# LTC4156Shield.net
KiCad netlist of a schematic drawn in EAGLE
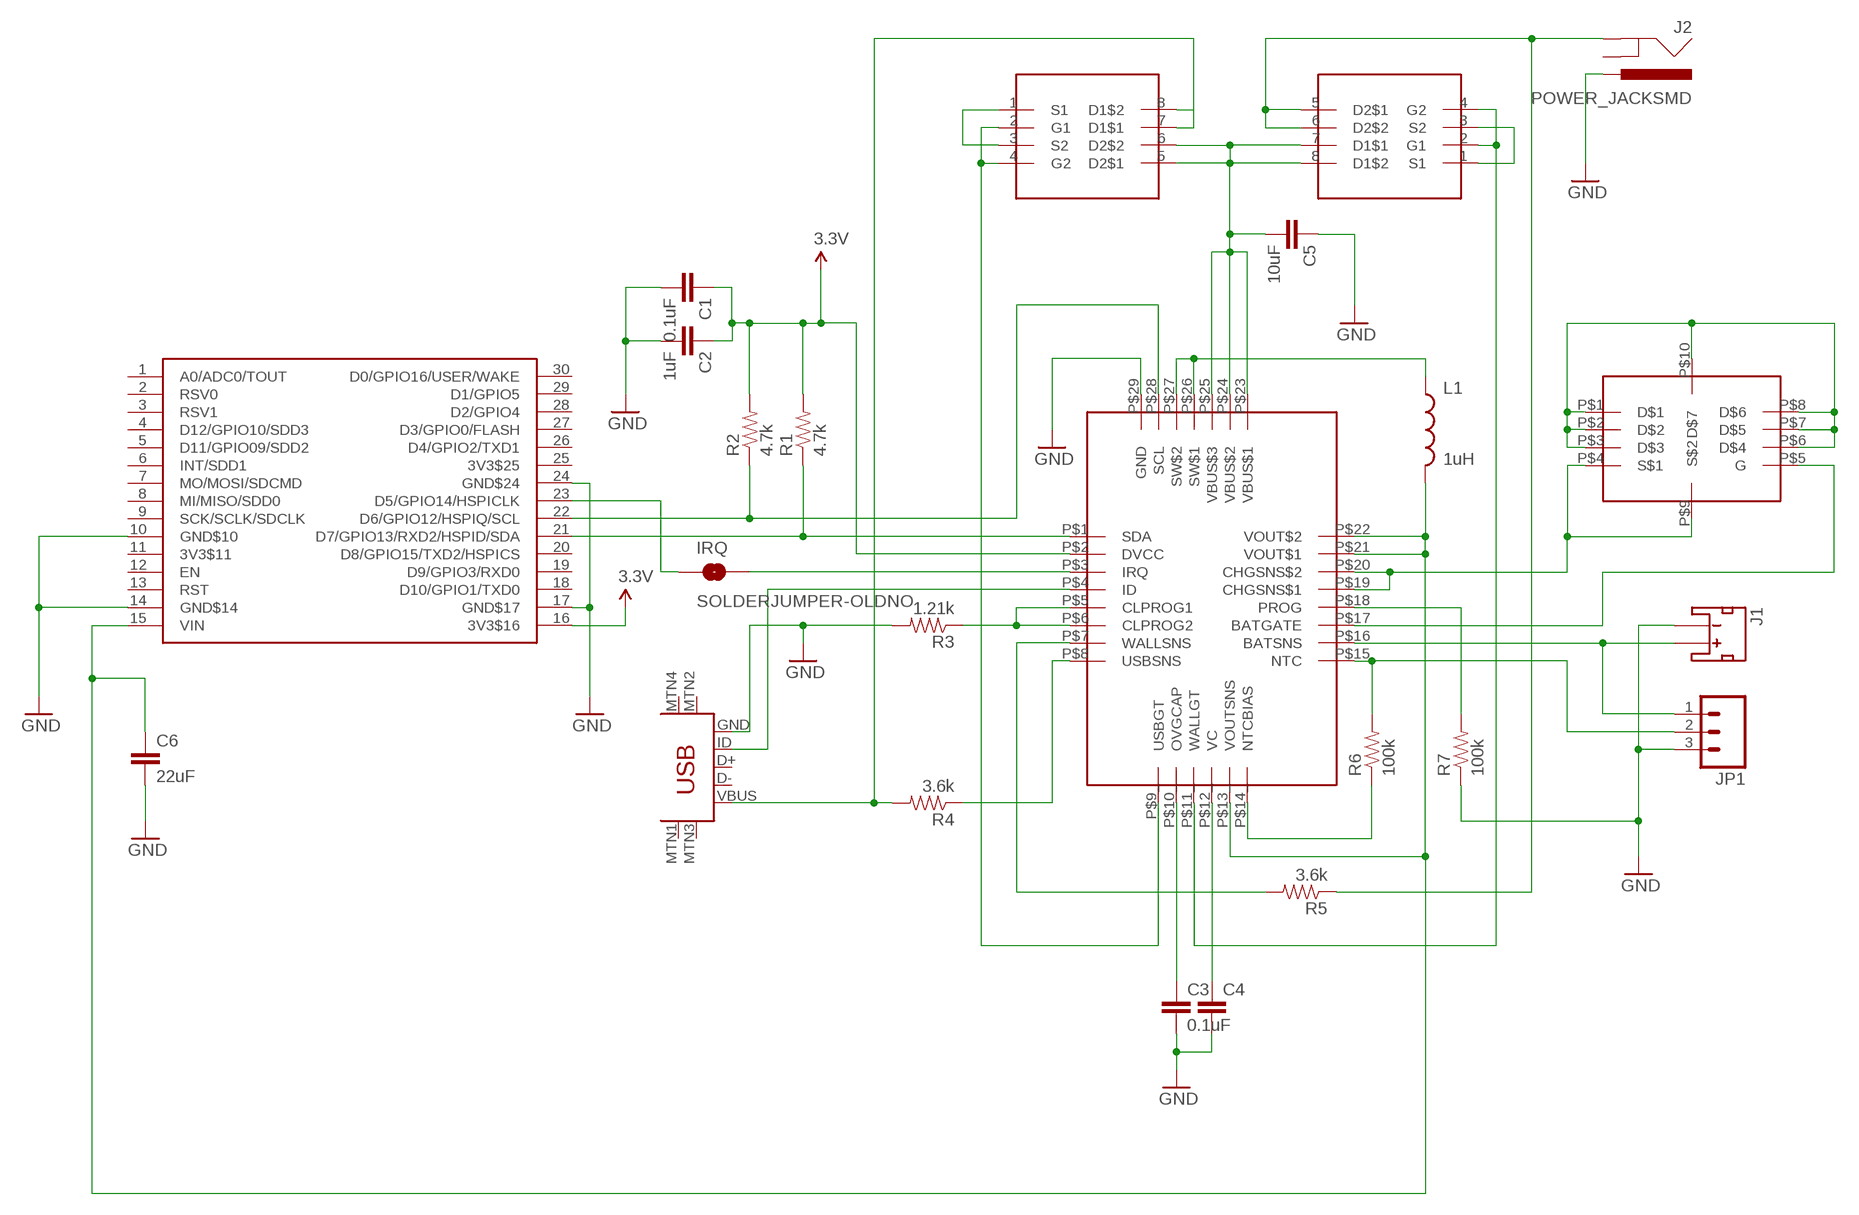
[diagram p0: schematic, sheet 1]

(export (version "E")
  (design (tool "Eeschema 10.0.6"))
  (components
    (comp (ref "C1")
      (value "0.1uF")
      (footprint "eagle-import:0402-CAP")
      (libsource (lib "eagle-import") (part "CAP0402-CAP"))
    )
    (comp (ref "C2")
      (value "1uF")
      (footprint "eagle-import:0402-CAP")
      (libsource (lib "eagle-import") (part "CAP0402-CAP"))
    )
    (comp (ref "C3")
      (value "0.1uF")
      (footprint "eagle-import:0402-CAP")
      (libsource (lib "eagle-import") (part "CAP0402-CAP"))
    )
    (comp (ref "C4")
      (value "CAP0805")
      (footprint "eagle-import:0805")
      (libsource (lib "eagle-import") (part "SparkFun-Capacitors_CAP0805"))
    )
    (comp (ref "C5")
      (value "10uF")
      (footprint "eagle-import:0402-CAP")
      (libsource (lib "eagle-import") (part "CAP0402-CAP"))
    )
    (comp (ref "C6")
      (value "22uF")
      (footprint "eagle-import:0402-CAP")
      (libsource (lib "eagle-import") (part "CAP0402-CAP"))
    )
    (comp (ref "IRQ")
      (value "SOLDERJUMPER-OLDNO")
      (footprint "eagle-import:SJ_2S-NO")
      (libsource (lib "eagle-import") (part "SOLDERJUMPER-OLDNO"))
    )
    (comp (ref "J1")
      (value "JST_2MM_MALE")
      (footprint "eagle-import:JST-2-SMD")
      (libsource (lib "eagle-import") (part "JST_2MM_MALE"))
    )
    (comp (ref "J2")
      (value "POWER_JACKSMD")
      (footprint "eagle-import:POWER_JACK_SMD")
      (libsource (lib "eagle-import") (part "POWER_JACKSMD"))
    )
    (comp (ref "JP1")
      (value "M03")
      (footprint "eagle-import:JST-3-SMD")
      (libsource (lib "eagle-import") (part "M03"))
    )
    (comp (ref "L1")
      (value "1uH")
      (footprint "eagle-import:0805")
      (libsource (lib "eagle-import") (part "INDUCTOR0805"))
    )
    (comp (ref "R1")
      (value "4.7k")
      (footprint "eagle-import:0402-RES")
      (libsource (lib "eagle-import") (part "RESISTOR0402-RES"))
    )
    (comp (ref "R2")
      (value "4.7k")
      (footprint "eagle-import:0402-RES")
      (libsource (lib "eagle-import") (part "RESISTOR0402-RES"))
    )
    (comp (ref "R3")
      (value "1.21k")
      (footprint "eagle-import:0402-RES")
      (libsource (lib "eagle-import") (part "RESISTOR0402-RES"))
    )
    (comp (ref "R4")
      (value "3.6k")
      (footprint "eagle-import:0402-RES")
      (libsource (lib "eagle-import") (part "RESISTOR0402-RES"))
    )
    (comp (ref "R5")
      (value "3.6k")
      (footprint "eagle-import:0402-RES")
      (libsource (lib "eagle-import") (part "RESISTOR0402-RES"))
    )
    (comp (ref "R6")
      (value "100k")
      (footprint "eagle-import:0402-RES")
      (libsource (lib "eagle-import") (part "RESISTOR0402-RES"))
    )
    (comp (ref "R7")
      (value "100k")
      (footprint "eagle-import:0402-RES")
      (libsource (lib "eagle-import") (part "RESISTOR0402-RES"))
    )
    (comp (ref "U$1")
      (value "NERDSHIELD")
      (footprint "eagle-import:NERDUINO_STACK")
      (libsource (lib "eagle-import") (part "NERDSHIELD"))
    )
    (comp (ref "U$2")
      (value "LTC4156")
      (footprint "eagle-import:QFN28")
      (libsource (lib "eagle-import") (part "LTC4156"))
    )
    (comp (ref "U$3")
      (value "SI7938DP")
      (footprint "eagle-import:SO08")
      (libsource (lib "eagle-import") (part "SI7938DP"))
    )
    (comp (ref "U$4")
      (value "USB-MINIB-5PIN")
      (footprint "eagle-import:USB-MINIB")
      (libsource (lib "eagle-import") (part "USB-MINIB-5PIN"))
    )
    (comp (ref "U$5")
      (value "SI7938DP")
      (footprint "eagle-import:SO08")
      (libsource (lib "eagle-import") (part "SI7938DP"))
    )
    (comp (ref "U$6")
      (value "SI5481")
      (footprint "eagle-import:SI5481")
      (libsource (lib "eagle-import") (part "SI5481"))
    )
  )
  (nets
    (net (code "1") (name "3.3V") (class "Default")
      (node (ref "C1") (pin "1") (pinfunction "1_1") (pintype "passive"))
      (node (ref "C2") (pin "1") (pinfunction "1_1") (pintype "passive"))
      (node (ref "R1") (pin "2") (pinfunction "2_2") (pintype "passive"))
      (node (ref "R2") (pin "2") (pinfunction "2_2") (pintype "passive"))
      (node (ref "U$1") (pin "16") (pinfunction "3V3$16_16") (pintype "bidirectional"))
      (node (ref "U$2") (pin "P$2") (pinfunction "DVCC_P$2") (pintype "bidirectional"))
    )
    (net (code "2") (name "GND") (class "Default")
      (node (ref "C1") (pin "2") (pinfunction "2_2") (pintype "passive"))
      (node (ref "C2") (pin "2") (pinfunction "2_2") (pintype "passive"))
      (node (ref "C3") (pin "2") (pinfunction "2_2") (pintype "passive"))
      (node (ref "C4") (pin "2") (pinfunction "2_2") (pintype "passive"))
      (node (ref "C5") (pin "1") (pinfunction "1_1") (pintype "passive"))
      (node (ref "C6") (pin "2") (pinfunction "2_2") (pintype "passive"))
      (node (ref "J1") (pin "1") (pinfunction "-_1") (pintype "bidirectional"))
      (node (ref "J2") (pin "VIN0") (pinfunction "PWR_VIN0") (pintype "bidirectional"))
      (node (ref "JP1") (pin "3") (pinfunction "3_3") (pintype "passive"))
      (node (ref "R3") (pin "2") (pinfunction "2_2") (pintype "passive"))
      (node (ref "R7") (pin "1") (pinfunction "1_1") (pintype "passive"))
      (node (ref "U$1") (pin "10") (pinfunction "GND$10_10") (pintype "bidirectional"))
      (node (ref "U$1") (pin "14") (pinfunction "GND$14_14") (pintype "bidirectional"))
      (node (ref "U$1") (pin "17") (pinfunction "GND$17_17") (pintype "bidirectional"))
      (node (ref "U$1") (pin "24") (pinfunction "GND$24_24") (pintype "bidirectional"))
      (node (ref "U$2") (pin "P$29") (pinfunction "GND_P$29") (pintype "bidirectional"))
      (node (ref "U$4") (pin "GND") (pinfunction "GND_GND") (pintype "bidirectional"))
    )
    (net (code "3") (name "Net-(J1-+)") (class "Default")
      (node (ref "J1") (pin "2") (pinfunction "+_2") (pintype "bidirectional"))
      (node (ref "JP1") (pin "1") (pinfunction "1_1") (pintype "passive"))
      (node (ref "U$2") (pin "P$16") (pinfunction "BATSNS_P$16") (pintype "bidirectional"))
    )
    (net (code "4") (name "Net-(J2-GND)") (class "Default")
      (node (ref "J2") (pin "P$4") (pinfunction "GND_P$4") (pintype "bidirectional"))
      (node (ref "R5") (pin "1") (pinfunction "1_1") (pintype "passive"))
      (node (ref "U$5") (pin "5") (pinfunction "D2$1_5") (pintype "bidirectional"))
      (node (ref "U$5") (pin "6") (pinfunction "D2$2_6") (pintype "bidirectional"))
    )
    (net (code "5") (name "Net-(U$1-D5{slash}GPIO14{slash}HSPICLK)") (class "Default")
      (node (ref "IRQ") (pin "1") (pinfunction "1_1") (pintype "passive"))
      (node (ref "U$1") (pin "23") (pinfunction "D5/GPIO14/HSPICLK_23") (pintype "bidirectional"))
    )
    (net (code "6") (name "Net-(U$1-D6{slash}GPIO12{slash}HSPIQ{slash}SCL)") (class "Default")
      (node (ref "R2") (pin "1") (pinfunction "1_1") (pintype "passive"))
      (node (ref "U$1") (pin "22") (pinfunction "D6/GPIO12/HSPIQ/SCL_22") (pintype "bidirectional"))
      (node (ref "U$2") (pin "P$28") (pinfunction "SCL_P$28") (pintype "bidirectional"))
    )
    (net (code "7") (name "Net-(U$1-D7{slash}GPIO13{slash}RXD2{slash}HSPID{slash}SDA)") (class "Default")
      (node (ref "R1") (pin "1") (pinfunction "1_1") (pintype "passive"))
      (node (ref "U$1") (pin "21") (pinfunction "D7/GPIO13/RXD2/HSPID/SDA_21") (pintype "bidirectional"))
      (node (ref "U$2") (pin "P$1") (pinfunction "SDA_P$1") (pintype "bidirectional"))
    )
    (net (code "8") (name "Net-(U$1-VIN)") (class "Default")
      (node (ref "C6") (pin "1") (pinfunction "1_1") (pintype "passive"))
      (node (ref "L1") (pin "2") (pinfunction "2_2") (pintype "passive"))
      (node (ref "U$1") (pin "15") (pinfunction "VIN_15") (pintype "bidirectional"))
      (node (ref "U$2") (pin "P$13_") (pinfunction "VOUTSNS_P$13_") (pintype "bidirectional"))
      (node (ref "U$2") (pin "P$21") (pinfunction "VOUT$1_P$21") (pintype "bidirectional"))
      (node (ref "U$2") (pin "P$22") (pinfunction "VOUT$2_P$22") (pintype "bidirectional"))
    )
    (net (code "9") (name "Net-(U$2-BATGATE)") (class "Default")
      (node (ref "U$2") (pin "P$17") (pinfunction "BATGATE_P$17") (pintype "bidirectional"))
      (node (ref "U$6") (pin "P$5") (pinfunction "G_P$5") (pintype "bidirectional"))
    )
    (net (code "10") (name "Net-(U$2-CHGSNS$1)") (class "Default")
      (node (ref "U$2") (pin "P$19") (pinfunction "CHGSNS$1_P$19") (pintype "bidirectional"))
      (node (ref "U$2") (pin "P$20") (pinfunction "CHGSNS$2_P$20") (pintype "bidirectional"))
      (node (ref "U$6") (pin "P$4") (pinfunction "S$1_P$4") (pintype "bidirectional"))
      (node (ref "U$6") (pin "P$9") (pinfunction "S$2_P$9") (pintype "bidirectional"))
    )
    (net (code "11") (name "Net-(U$2-CLPROG1)") (class "Default")
      (node (ref "R3") (pin "1") (pinfunction "1_1") (pintype "passive"))
      (node (ref "U$2") (pin "P$5") (pinfunction "CLPROG1_P$5") (pintype "bidirectional"))
      (node (ref "U$2") (pin "P$6") (pinfunction "CLPROG2_P$6") (pintype "bidirectional"))
    )
    (net (code "12") (name "Net-(U$2-ID)") (class "Default")
      (node (ref "U$2") (pin "P$4") (pinfunction "ID_P$4") (pintype "bidirectional"))
      (node (ref "U$4") (pin "ID") (pinfunction "ID_ID") (pintype "bidirectional"))
    )
    (net (code "13") (name "Net-(U$2-IRQ)") (class "Default")
      (node (ref "IRQ") (pin "2") (pinfunction "2_2") (pintype "passive"))
      (node (ref "U$2") (pin "P$3") (pinfunction "IRQ_P$3") (pintype "bidirectional"))
    )
    (net (code "14") (name "Net-(U$2-NTC)") (class "Default")
      (node (ref "JP1") (pin "2") (pinfunction "2_2") (pintype "passive"))
      (node (ref "R6") (pin "2") (pinfunction "2_2") (pintype "passive"))
      (node (ref "U$2") (pin "P$15") (pinfunction "NTC_P$15") (pintype "bidirectional"))
    )
    (net (code "15") (name "Net-(U$2-NTCBIAS)") (class "Default")
      (node (ref "R6") (pin "1") (pinfunction "1_1") (pintype "passive"))
      (node (ref "U$2") (pin "P$14_") (pinfunction "NTCBIAS_P$14_") (pintype "bidirectional"))
    )
    (net (code "16") (name "Net-(U$2-OVGCAP)") (class "Default")
      (node (ref "C3") (pin "1") (pinfunction "1_1") (pintype "passive"))
      (node (ref "U$2") (pin "P$10_") (pinfunction "OVGCAP_P$10_") (pintype "bidirectional"))
    )
    (net (code "17") (name "Net-(U$2-PROG)") (class "Default")
      (node (ref "R7") (pin "2") (pinfunction "2_2") (pintype "passive"))
      (node (ref "U$2") (pin "P$18") (pinfunction "PROG_P$18") (pintype "bidirectional"))
    )
    (net (code "18") (name "Net-(U$2-SW$1)") (class "Default")
      (node (ref "L1") (pin "1") (pinfunction "1_1") (pintype "passive"))
      (node (ref "U$2") (pin "P$26") (pinfunction "SW$1_P$26") (pintype "bidirectional"))
      (node (ref "U$2") (pin "P$27") (pinfunction "SW$2_P$27") (pintype "bidirectional"))
    )
    (net (code "19") (name "Net-(U$2-USBGT)") (class "Default")
      (node (ref "U$2") (pin "P$9_") (pinfunction "USBGT_P$9_") (pintype "bidirectional"))
      (node (ref "U$3") (pin "2") (pinfunction "G1_2") (pintype "bidirectional"))
      (node (ref "U$3") (pin "4") (pinfunction "G2_4") (pintype "bidirectional"))
    )
    (net (code "20") (name "Net-(U$2-USBSNS)") (class "Default")
      (node (ref "R4") (pin "1") (pinfunction "1_1") (pintype "passive"))
      (node (ref "U$2") (pin "P$8") (pinfunction "USBSNS_P$8") (pintype "bidirectional"))
    )
    (net (code "21") (name "Net-(U$2-VBUS$1)") (class "Default")
      (node (ref "C5") (pin "2") (pinfunction "2_2") (pintype "passive"))
      (node (ref "U$2") (pin "P$23") (pinfunction "VBUS$1_P$23") (pintype "bidirectional"))
      (node (ref "U$2") (pin "P$24") (pinfunction "VBUS$2_P$24") (pintype "bidirectional"))
      (node (ref "U$2") (pin "P$25") (pinfunction "VBUS$3_P$25") (pintype "bidirectional"))
      (node (ref "U$3") (pin "5") (pinfunction "D2$1_5") (pintype "bidirectional"))
      (node (ref "U$3") (pin "6") (pinfunction "D2$2_6") (pintype "bidirectional"))
      (node (ref "U$5") (pin "7") (pinfunction "D1$1_7") (pintype "bidirectional"))
      (node (ref "U$5") (pin "8") (pinfunction "D1$2_8") (pintype "bidirectional"))
    )
    (net (code "22") (name "Net-(U$2-VC)") (class "Default")
      (node (ref "C4") (pin "1") (pinfunction "1_1") (pintype "passive"))
      (node (ref "U$2") (pin "P$12_") (pinfunction "VC_P$12_") (pintype "bidirectional"))
    )
    (net (code "23") (name "Net-(U$2-WALLGT)") (class "Default")
      (node (ref "U$2") (pin "P$11_") (pinfunction "WALLGT_P$11_") (pintype "bidirectional"))
      (node (ref "U$5") (pin "2") (pinfunction "G1_2") (pintype "bidirectional"))
      (node (ref "U$5") (pin "4") (pinfunction "G2_4") (pintype "bidirectional"))
    )
    (net (code "24") (name "Net-(U$2-WALLSNS)") (class "Default")
      (node (ref "R5") (pin "2") (pinfunction "2_2") (pintype "passive"))
      (node (ref "U$2") (pin "P$7") (pinfunction "WALLSNS_P$7") (pintype "bidirectional"))
    )
    (net (code "25") (name "Net-(U$3-D1$1)") (class "Default")
      (node (ref "R4") (pin "2") (pinfunction "2_2") (pintype "passive"))
      (node (ref "U$3") (pin "7") (pinfunction "D1$1_7") (pintype "bidirectional"))
      (node (ref "U$3") (pin "8") (pinfunction "D1$2_8") (pintype "bidirectional"))
      (node (ref "U$4") (pin "VBUS") (pinfunction "VBUS_VBUS") (pintype "bidirectional"))
    )
    (net (code "26") (name "Net-(U$3-S1)") (class "Default")
      (node (ref "U$3") (pin "1") (pinfunction "S1_1") (pintype "bidirectional"))
      (node (ref "U$3") (pin "3") (pinfunction "S2_3") (pintype "bidirectional"))
    )
    (net (code "27") (name "Net-(U$5-S1)") (class "Default")
      (node (ref "U$5") (pin "1") (pinfunction "S1_1") (pintype "bidirectional"))
      (node (ref "U$5") (pin "3") (pinfunction "S2_3") (pintype "bidirectional"))
    )
    (net (code "28") (name "Net-(U$6-D$1)") (class "Default")
      (node (ref "U$6") (pin "P$1") (pinfunction "D$1_P$1") (pintype "bidirectional"))
      (node (ref "U$6") (pin "P$10") (pinfunction "D$7_P$10") (pintype "bidirectional"))
      (node (ref "U$6") (pin "P$2") (pinfunction "D$2_P$2") (pintype "bidirectional"))
      (node (ref "U$6") (pin "P$3") (pinfunction "D$3_P$3") (pintype "bidirectional"))
      (node (ref "U$6") (pin "P$6") (pinfunction "D$4_P$6") (pintype "bidirectional"))
      (node (ref "U$6") (pin "P$7") (pinfunction "D$5_P$7") (pintype "bidirectional"))
      (node (ref "U$6") (pin "P$8") (pinfunction "D$6_P$8") (pintype "bidirectional"))
    )
    (net (code "29") (name "unconnected-(J1-PAD1-PadNC1)") (class "Default")
      (node (ref "J1") (pin "NC1") (pinfunction "PAD1_NC1") (pintype "bidirectional"))
    )
    (net (code "30") (name "unconnected-(J1-PAD2-PadNC2)") (class "Default")
      (node (ref "J1") (pin "NC2") (pinfunction "PAD2_NC2") (pintype "bidirectional"))
    )
    (net (code "31") (name "unconnected-(J2-GNDBREAK-PadGND)") (class "Default")
      (node (ref "J2") (pin "GND") (pinfunction "GNDBREAK_GND") (pintype "bidirectional"))
    )
    (net (code "32") (name "unconnected-(U$1-3V3$11-Pad11)") (class "Default")
      (node (ref "U$1") (pin "11") (pinfunction "3V3$11_11") (pintype "bidirectional"))
    )
    (net (code "33") (name "unconnected-(U$1-3V3$25-Pad25)") (class "Default")
      (node (ref "U$1") (pin "25") (pinfunction "3V3$25_25") (pintype "bidirectional"))
    )
    (net (code "34") (name "unconnected-(U$1-A0{slash}ADC0{slash}TOUT-Pad1)") (class "Default")
      (node (ref "U$1") (pin "1") (pinfunction "A0/ADC0/TOUT_1") (pintype "bidirectional"))
    )
    (net (code "35") (name "unconnected-(U$1-D0{slash}GPIO16{slash}USER{slash}WAKE-Pad30)") (class "Default")
      (node (ref "U$1") (pin "30") (pinfunction "D0/GPIO16/USER/WAKE_30") (pintype "bidirectional"))
    )
    (net (code "36") (name "unconnected-(U$1-D1{slash}GPIO5-Pad29)") (class "Default")
      (node (ref "U$1") (pin "29") (pinfunction "D1/GPIO5_29") (pintype "bidirectional"))
    )
    (net (code "37") (name "unconnected-(U$1-D2{slash}GPIO4-Pad28)") (class "Default")
      (node (ref "U$1") (pin "28") (pinfunction "D2/GPIO4_28") (pintype "bidirectional"))
    )
    (net (code "38") (name "unconnected-(U$1-D3{slash}GPIO0{slash}FLASH-Pad27)") (class "Default")
      (node (ref "U$1") (pin "27") (pinfunction "D3/GPIO0/FLASH_27") (pintype "bidirectional"))
    )
    (net (code "39") (name "unconnected-(U$1-D4{slash}GPIO2{slash}TXD1-Pad26)") (class "Default")
      (node (ref "U$1") (pin "26") (pinfunction "D4/GPIO2/TXD1_26") (pintype "bidirectional"))
    )
    (net (code "40") (name "unconnected-(U$1-D8{slash}GPIO15{slash}TXD2{slash}HSPICS-Pad20)") (class "Default")
      (node (ref "U$1") (pin "20") (pinfunction "D8/GPIO15/TXD2/HSPICS_20") (pintype "bidirectional"))
    )
    (net (code "41") (name "unconnected-(U$1-D9{slash}GPIO3{slash}RXD0-Pad19)") (class "Default")
      (node (ref "U$1") (pin "19") (pinfunction "D9/GPIO3/RXD0_19") (pintype "bidirectional"))
    )
    (net (code "42") (name "unconnected-(U$1-D10{slash}GPIO1{slash}TXD0-Pad18)") (class "Default")
      (node (ref "U$1") (pin "18") (pinfunction "D10/GPIO1/TXD0_18") (pintype "bidirectional"))
    )
    (net (code "43") (name "unconnected-(U$1-D11{slash}GPIO09{slash}SDD2-Pad5)") (class "Default")
      (node (ref "U$1") (pin "5") (pinfunction "D11/GPIO09/SDD2_5") (pintype "bidirectional"))
    )
    (net (code "44") (name "unconnected-(U$1-D12{slash}GPIO10{slash}SDD3-Pad4)") (class "Default")
      (node (ref "U$1") (pin "4") (pinfunction "D12/GPIO10/SDD3_4") (pintype "bidirectional"))
    )
    (net (code "45") (name "unconnected-(U$1-EN-Pad12)") (class "Default")
      (node (ref "U$1") (pin "12") (pinfunction "EN_12") (pintype "bidirectional"))
    )
    (net (code "46") (name "unconnected-(U$1-INT{slash}SDD1-Pad6)") (class "Default")
      (node (ref "U$1") (pin "6") (pinfunction "INT/SDD1_6") (pintype "bidirectional"))
    )
    (net (code "47") (name "unconnected-(U$1-MI{slash}MISO{slash}SDD0-Pad8)") (class "Default")
      (node (ref "U$1") (pin "8") (pinfunction "MI/MISO/SDD0_8") (pintype "bidirectional"))
    )
    (net (code "48") (name "unconnected-(U$1-MO{slash}MOSI{slash}SDCMD-Pad7)") (class "Default")
      (node (ref "U$1") (pin "7") (pinfunction "MO/MOSI/SDCMD_7") (pintype "bidirectional"))
    )
    (net (code "49") (name "unconnected-(U$1-RST-Pad13)") (class "Default")
      (node (ref "U$1") (pin "13") (pinfunction "RST_13") (pintype "bidirectional"))
    )
    (net (code "50") (name "unconnected-(U$1-RSV0-Pad2)") (class "Default")
      (node (ref "U$1") (pin "2") (pinfunction "RSV0_2") (pintype "bidirectional"))
    )
    (net (code "51") (name "unconnected-(U$1-RSV1-Pad3)") (class "Default")
      (node (ref "U$1") (pin "3") (pinfunction "RSV1_3") (pintype "bidirectional"))
    )
    (net (code "52") (name "unconnected-(U$1-SCK{slash}SCLK{slash}SDCLK-Pad9)") (class "Default")
      (node (ref "U$1") (pin "9") (pinfunction "SCK/SCLK/SDCLK_9") (pintype "bidirectional"))
    )
    (net (code "53") (name "unconnected-(U$4-MTN1-PadMTN3)") (class "Default")
      (node (ref "U$4") (pin "MTN3") (pinfunction "MTN1_MTN3") (pintype "bidirectional"))
    )
    (net (code "54") (name "unconnected-(U$4-MTN2-PadMTN1)") (class "Default")
      (node (ref "U$4") (pin "MTN1") (pinfunction "MTN2_MTN1") (pintype "bidirectional"))
    )
    (net (code "55") (name "unconnected-(U$4-MTN3-PadMTN2)") (class "Default")
      (node (ref "U$4") (pin "MTN2") (pinfunction "MTN3_MTN2") (pintype "bidirectional"))
    )
    (net (code "56") (name "unconnected-(U$4-PadD+)") (class "Default")
      (node (ref "U$4") (pin "D+") (pinfunction "D+_D+") (pintype "bidirectional"))
    )
    (net (code "57") (name "unconnected-(U$4-PadD-)") (class "Default")
      (node (ref "U$4") (pin "D-") (pinfunction "D-_D-") (pintype "bidirectional"))
    )
    (net (code "58") (name "unconnected-(U$4-PadMTN4)") (class "Default")
      (node (ref "U$4") (pin "MTN4") (pinfunction "MTN4_MTN4") (pintype "bidirectional"))
    )
  )
)
